# power_supply.net
KiCad netlist of a schematic drawn in Altium Designer
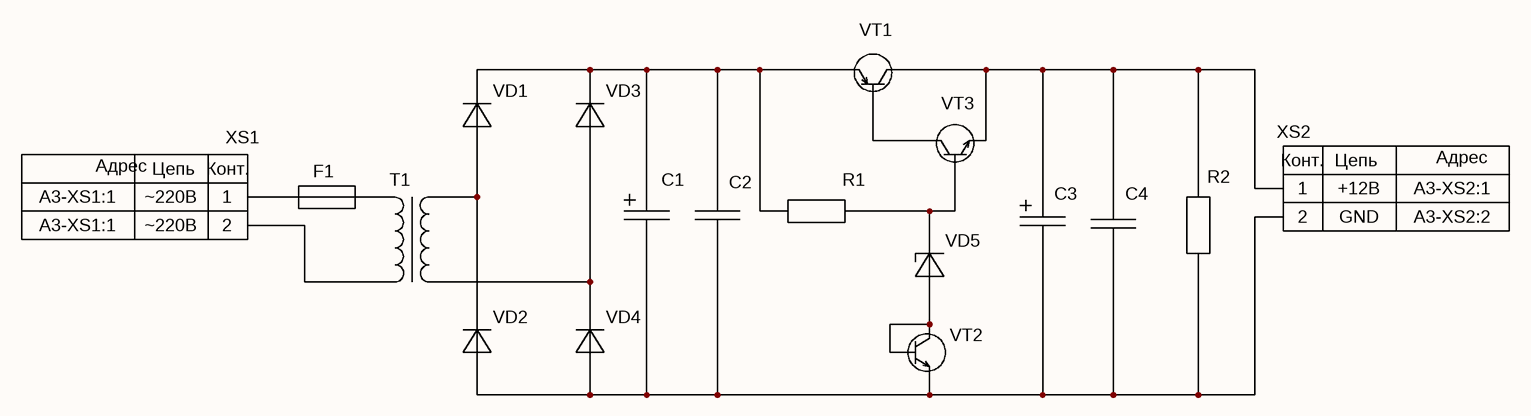
[diagram p0: power_supply.SchDoc]

(export (version "E")
  (design (tool "Eeschema 10.0.6"))
  (components
    (comp (ref "C1") (value "1000 мкФ") (footprint "CAP: D10C5H20") (libsource (lib "elems") (part "C_pol")))
    (comp (ref "C2") (value "100 нФ") (footprint "CAP: 1206") (libsource (lib "elems") (part "C_const")))
    (comp (ref "C3")
      (value "220 мкФ")
      (footprint "CAP: D6.3C2.5H11")
      (libsource (lib "elems") (part "C_pol"))
    )
    (comp (ref "C4") (value "100нФ") (footprint "CAP: 1206") (libsource (lib "elems") (part "C_const")))
    (comp (ref "F1")
      (value "0.5 А")
      (footprint "FUSE: 0679H (BelFuse)")
      (libsource (lib "elems") (part "fuse"))
    )
    (comp (ref "R1") (value "330 Ом") (footprint "RES: 1206") (libsource (lib "elems") (part "Res")))
    (comp (ref "R2") (value "1 кОм") (footprint "RES: 1206") (libsource (lib "elems") (part "Res")))
    (comp (ref "T1")
      (value "Trans_1_1")
      (footprint "15v_0.7A_trans")
      (libsource (lib "elems") (part "Trans_1_1"))
    )
    (comp (ref "VD1") (value "1n5400") (footprint "1n5400-1n5408") (libsource (lib "elems") (part "VD")))
    (comp (ref "VD2") (value "1n5400") (footprint "1n5400-1n5408") (libsource (lib "elems") (part "VD")))
    (comp (ref "VD3") (value "1n5400") (footprint "1n5400-1n5408") (libsource (lib "elems") (part "VD")))
    (comp (ref "VD4") (value "1n5400") (footprint "1n5400-1n5408") (libsource (lib "elems") (part "VD")))
    (comp (ref "VD5") (value "1n4742") (footprint "1n4728-1n4764") (libsource (lib "elems") (part "zener")))
    (comp (ref "VT1") (value "2SB1132T100Q") (footprint "SOT89") (libsource (lib "elems") (part "pnp")))
    (comp (ref "VT2") (value "2n4401") (footprint "TO-92") (libsource (lib "elems") (part "npn")))
    (comp (ref "VT3") (value "2n4401") (footprint "TO-92") (libsource (lib "elems") (part "npn")))
    (comp (ref "XS1")
      (value "X2")
      (footprint "CON: DG350-3.5-02P")
      (fields
        (field (name "CIRCUIT2") "~220В")
        (field (name "CIRCUIT1") "~220В")
        (field (name "=ADDRESS2") "A3-XS1:1")
        (field (name "=ADDRESS1") "A3-XS1:1")
      )
      (libsource (lib "elems") (part "X2"))
    )
    (comp (ref "XS2")
      (value "X2")
      (footprint "CON: CWF-2")
      (fields
        (field (name "CIRCUIT2") "GND")
        (field (name "CIRCUIT1") "+12В")
        (field (name "=ADDRESS2") "A3-XS2:2")
        (field (name "=ADDRESS1") "A3-XS2:1")
      )
      (libsource (lib "elems") (part "X2"))
    )
  )
  (nets
    (net (code "1") (name "Net-(F1-Pad1)") (class "Default")
      (node (ref "F1") (pin "1") (pinfunction "1_1") (pintype "passive"))
      (node (ref "XS1") (pin "1") (pinfunction "1_1") (pintype "passive"))
    )
    (net (code "2") (name "Net-(F1-Pad2)") (class "Default")
      (node (ref "F1") (pin "2") (pinfunction "2_2") (pintype "passive"))
      (node (ref "T1") (pin "1") (pinfunction "1_1") (pintype "passive"))
    )
    (net (code "3") (name "Net-(R1-6)") (class "Default")
      (node (ref "R1") (pin "2") (pinfunction "6_2") (pintype "passive"))
      (node (ref "VD5") (pin "2") (pinfunction "2_2") (pintype "passive"))
      (node (ref "VT3") (pin "1") (pinfunction "b_1") (pintype "passive"))
    )
    (net (code "4") (name "Net-(R2-6)") (class "Default")
      (node (ref "C3") (pin "1") (pinfunction "1_1") (pintype "passive"))
      (node (ref "C4") (pin "1") (pinfunction "1_1") (pintype "passive"))
      (node (ref "R2") (pin "2") (pinfunction "6_2") (pintype "passive"))
      (node (ref "VT1") (pin "2") (pinfunction "c_2") (pintype "passive"))
      (node (ref "VT3") (pin "3") (pinfunction "e_3") (pintype "passive"))
      (node (ref "XS2") (pin "1") (pinfunction "1_1") (pintype "passive"))
    )
    (net (code "5") (name "Net-(T1-Pad2)") (class "Default")
      (node (ref "T1") (pin "2") (pinfunction "2_2") (pintype "passive"))
      (node (ref "XS1") (pin "2") (pinfunction "2_2") (pintype "passive"))
    )
    (net (code "6") (name "Net-(T1-Pad3)") (class "Default")
      (node (ref "T1") (pin "3") (pinfunction "3_3") (pintype "passive"))
      (node (ref "VD1") (pin "1") (pinfunction "1_1") (pintype "passive"))
      (node (ref "VD2") (pin "2") (pinfunction "2_2") (pintype "passive"))
    )
    (net (code "7") (name "Net-(T1-Pad4)") (class "Default")
      (node (ref "T1") (pin "4") (pinfunction "4_4") (pintype "passive"))
      (node (ref "VD3") (pin "1") (pinfunction "1_1") (pintype "passive"))
      (node (ref "VD4") (pin "2") (pinfunction "2_2") (pintype "passive"))
    )
    (net (code "8") (name "Net-(VT1-b)") (class "Default")
      (node (ref "VT1") (pin "1") (pinfunction "b_1") (pintype "passive"))
      (node (ref "VT3") (pin "2") (pinfunction "c_2") (pintype "passive"))
    )
    (net (code "9") (name "Net-(VT1-e)") (class "Default")
      (node (ref "C1") (pin "1") (pinfunction "1_1") (pintype "passive"))
      (node (ref "C2") (pin "2") (pinfunction "2_2") (pintype "passive"))
      (node (ref "R1") (pin "1") (pinfunction "1_1") (pintype "passive"))
      (node (ref "VD1") (pin "2") (pinfunction "2_2") (pintype "passive"))
      (node (ref "VD3") (pin "2") (pinfunction "2_2") (pintype "passive"))
      (node (ref "VT1") (pin "3") (pinfunction "e_3") (pintype "passive"))
    )
    (net (code "10") (name "Net-(VT2-b)") (class "Default")
      (node (ref "VD5") (pin "1") (pinfunction "1_1") (pintype "passive"))
      (node (ref "VT2") (pin "1") (pinfunction "b_1") (pintype "passive"))
      (node (ref "VT2") (pin "2") (pinfunction "c_2") (pintype "passive"))
    )
    (net (code "11") (name "Net-(VT2-e)") (class "Default")
      (node (ref "C1") (pin "2") (pinfunction "2_2") (pintype "passive"))
      (node (ref "C2") (pin "1") (pinfunction "1_1") (pintype "passive"))
      (node (ref "C3") (pin "2") (pinfunction "2_2") (pintype "passive"))
      (node (ref "C4") (pin "2") (pinfunction "2_2") (pintype "passive"))
      (node (ref "R2") (pin "1") (pinfunction "1_1") (pintype "passive"))
      (node (ref "VD2") (pin "1") (pinfunction "1_1") (pintype "passive"))
      (node (ref "VD4") (pin "1") (pinfunction "1_1") (pintype "passive"))
      (node (ref "VT2") (pin "3") (pinfunction "e_3") (pintype "passive"))
      (node (ref "XS2") (pin "2") (pinfunction "2_2") (pintype "passive"))
    )
  )
)
